# 7-segment.net
KiCad netlist of a schematic drawn in EAGLE
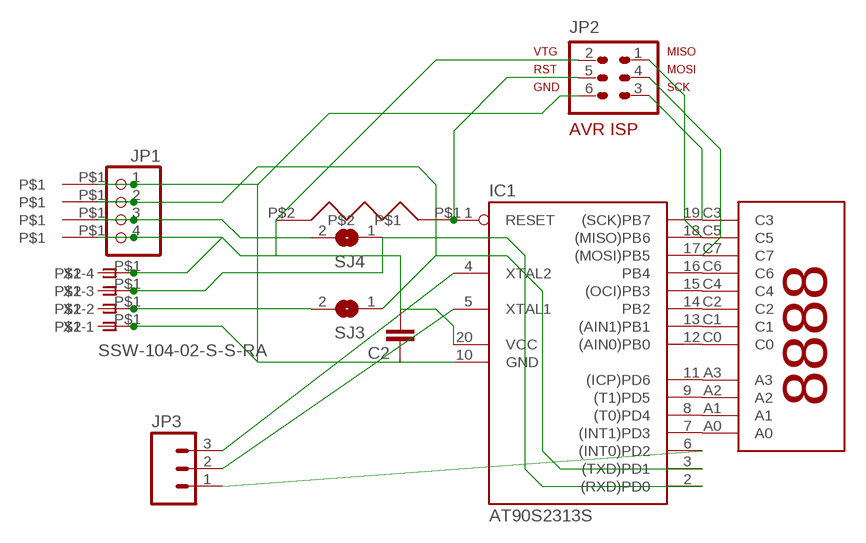
[diagram p0: schematic, sheet 1]

(export (version "E")
  (design (tool "Eeschema 10.0.6"))
  (components
    (comp (ref "C2")
      (value "CAPPTH")
      (footprint "eagle-import:CAP-PTH-SMALL")
      (libsource (lib "eagle-import") (part "CAPPTH"))
    )
    (comp (ref "IC1")
      (value "AT90S2313S")
      (footprint "eagle-import:SO20L")
      (libsource (lib "eagle-import") (part "AT90S2313S"))
    )
    (comp (ref "JP1")
      (value "PINHD-1X4/90")
      (footprint "eagle-import:1X04_90")
      (libsource (lib "eagle-import") (part "PINHD-1X4/90"))
    )
    (comp (ref "JP2")
      (value "AVR-ISP-6")
      (footprint "eagle-import:AVR-ISP-6")
      (libsource (lib "eagle-import") (part "AVR-ISP-6"))
    )
    (comp (ref "JP3")
      (value "M03PTH")
      (footprint "eagle-import:1X03")
      (libsource (lib "eagle-import") (part "M03PTH"))
    )
    (comp (ref "SJ3") (value "SJ") (footprint "eagle-import:SJ") (libsource (lib "eagle-import") (part "SJ")))
    (comp (ref "SJ4") (value "SJ") (footprint "eagle-import:SJ") (libsource (lib "eagle-import") (part "SJ")))
    (comp (ref "U$1")
      (value "7-SEGMENT-DISPLAY-5462-BS")
      (footprint "eagle-import:7SEG_5462BS")
      (libsource (lib "eagle-import") (part "7-SEGMENT-DISPLAY-5462-BS"))
    )
    (comp (ref "U$2")
      (value "R-6")
      (footprint "eagle-import:R-6")
      (libsource (lib "eagle-import") (part "R-6"))
    )
    (comp (ref "U$3")
      (value "WIREPAD_SQUARE_1")
      (footprint "eagle-import:WIREPAD_SQUARE_1")
      (libsource (lib "eagle-import") (part "WIREPAD_SQUARE_1"))
    )
    (comp (ref "U$4")
      (value "WIREPAD_SQUARE_1")
      (footprint "eagle-import:WIREPAD_SQUARE_1")
      (libsource (lib "eagle-import") (part "WIREPAD_SQUARE_1"))
    )
    (comp (ref "U$5")
      (value "WIREPAD_SQUARE_1")
      (footprint "eagle-import:WIREPAD_SQUARE_1")
      (libsource (lib "eagle-import") (part "WIREPAD_SQUARE_1"))
    )
    (comp (ref "U$6")
      (value "WIREPAD_SQUARE_1")
      (footprint "eagle-import:WIREPAD_SQUARE_1")
      (libsource (lib "eagle-import") (part "WIREPAD_SQUARE_1"))
    )
    (comp (ref "U$7")
      (value "WIREPAD_SQUARE_1")
      (footprint "eagle-import:WIREPAD_SQUARE_1")
      (libsource (lib "eagle-import") (part "WIREPAD_SQUARE_1"))
    )
    (comp (ref "U$8")
      (value "WIREPAD_SQUARE_1")
      (footprint "eagle-import:WIREPAD_SQUARE_1")
      (libsource (lib "eagle-import") (part "WIREPAD_SQUARE_1"))
    )
    (comp (ref "U$9")
      (value "WIREPAD_SQUARE_1")
      (footprint "eagle-import:WIREPAD_SQUARE_1")
      (libsource (lib "eagle-import") (part "WIREPAD_SQUARE_1"))
    )
    (comp (ref "U$10")
      (value "WIREPAD_SQUARE_1")
      (footprint "eagle-import:WIREPAD_SQUARE_1")
      (libsource (lib "eagle-import") (part "WIREPAD_SQUARE_1"))
    )
    (comp (ref "X2")
      (value "SSW-104-02-S-S-RA")
      (footprint "eagle-import:SSW-104-02-S-S-RA")
      (libsource (lib "eagle-import") (part "SSW-104-02-S-S-RA"))
    )
  )
  (nets
    (net (code "1") (name "Net-(IC1-(AIN0)PB0)") (class "Default")
      (node (ref "IC1") (pin "12") (pinfunction "(AIN0)PB0_12") (pintype "bidirectional"))
      (node (ref "U$1") (pin "C0") (pinfunction "C0_C0") (pintype "bidirectional"))
    )
    (net (code "2") (name "Net-(IC1-(AIN1)PB1)") (class "Default")
      (node (ref "IC1") (pin "13") (pinfunction "(AIN1)PB1_13") (pintype "bidirectional"))
      (node (ref "U$1") (pin "C1") (pinfunction "C1_C1") (pintype "bidirectional"))
    )
    (net (code "3") (name "Net-(IC1-(ICP)PD6)") (class "Default")
      (node (ref "IC1") (pin "11") (pinfunction "(ICP)PD6_11") (pintype "bidirectional"))
      (node (ref "U$1") (pin "A3") (pinfunction "A3_A3") (pintype "bidirectional"))
    )
    (net (code "4") (name "Net-(IC1-(INT0)PD2)") (class "Default")
      (node (ref "IC1") (pin "6") (pinfunction "(INT0)PD2_6") (pintype "bidirectional"))
      (node (ref "JP3") (pin "1") (pinfunction "1_1") (pintype "passive"))
    )
    (net (code "5") (name "Net-(IC1-(INT1)PD3)") (class "Default")
      (node (ref "IC1") (pin "7") (pinfunction "(INT1)PD3_7") (pintype "bidirectional"))
      (node (ref "U$1") (pin "A0") (pinfunction "A0_A0") (pintype "bidirectional"))
    )
    (net (code "6") (name "Net-(IC1-(MISO)PB6)") (class "Default")
      (node (ref "IC1") (pin "18") (pinfunction "(MISO)PB6_18") (pintype "bidirectional"))
      (node (ref "JP2") (pin "1") (pinfunction "1_1") (pintype "passive"))
      (node (ref "U$1") (pin "C5") (pinfunction "C5_C5") (pintype "bidirectional"))
    )
    (net (code "7") (name "Net-(IC1-(MOSI)PB5)") (class "Default")
      (node (ref "IC1") (pin "17") (pinfunction "(MOSI)PB5_17") (pintype "bidirectional"))
      (node (ref "JP2") (pin "4") (pinfunction "4_4") (pintype "passive"))
      (node (ref "U$1") (pin "C7") (pinfunction "C7_C7") (pintype "bidirectional"))
    )
    (net (code "8") (name "Net-(IC1-(OCI)PB3)") (class "Default")
      (node (ref "IC1") (pin "15") (pinfunction "(OCI)PB3_15") (pintype "bidirectional"))
      (node (ref "U$1") (pin "C4") (pinfunction "C4_C4") (pintype "bidirectional"))
    )
    (net (code "9") (name "Net-(IC1-(RXD)PD0)") (class "Default")
      (node (ref "IC1") (pin "2") (pinfunction "(RXD)PD0_2") (pintype "bidirectional"))
      (node (ref "SJ4") (pin "1") (pinfunction "1_1") (pintype "passive"))
      (node (ref "U$8") (pin "P$1") (pinfunction "P$1_P$1") (pintype "bidirectional"))
      (node (ref "X2") (pin "3") (pinfunction "1_3") (pintype "passive"))
    )
    (net (code "10") (name "Net-(IC1-(SCK)PB7)") (class "Default")
      (node (ref "IC1") (pin "19") (pinfunction "(SCK)PB7_19") (pintype "bidirectional"))
      (node (ref "JP2") (pin "3") (pinfunction "3_3") (pintype "passive"))
      (node (ref "U$1") (pin "C3") (pinfunction "C3_C3") (pintype "bidirectional"))
    )
    (net (code "11") (name "Net-(IC1-(T0)PD4)") (class "Default")
      (node (ref "IC1") (pin "8") (pinfunction "(T0)PD4_8") (pintype "bidirectional"))
      (node (ref "U$1") (pin "A1") (pinfunction "A1_A1") (pintype "bidirectional"))
    )
    (net (code "12") (name "Net-(IC1-(T1)PD5)") (class "Default")
      (node (ref "IC1") (pin "9") (pinfunction "(T1)PD5_9") (pintype "bidirectional"))
      (node (ref "U$1") (pin "A2") (pinfunction "A2_A2") (pintype "bidirectional"))
    )
    (net (code "13") (name "Net-(IC1-(TXD)PD1)") (class "Default")
      (node (ref "IC1") (pin "3") (pinfunction "(TXD)PD1_3") (pintype "bidirectional"))
      (node (ref "JP1") (pin "2") (pinfunction "2_2") (pintype "passive"))
      (node (ref "SJ3") (pin "1") (pinfunction "1_1") (pintype "passive"))
      (node (ref "U$4") (pin "P$1") (pinfunction "P$1_P$1") (pintype "bidirectional"))
    )
    (net (code "14") (name "Net-(IC1-GND)") (class "Default")
      (node (ref "C2") (pin "1") (pinfunction "1_1") (pintype "passive"))
      (node (ref "IC1") (pin "10") (pinfunction "GND_10") (pintype "power_in"))
      (node (ref "JP1") (pin "1") (pinfunction "1_1") (pintype "passive"))
      (node (ref "JP2") (pin "6") (pinfunction "6_6") (pintype "passive"))
      (node (ref "U$10") (pin "P$1") (pinfunction "P$1_P$1") (pintype "bidirectional"))
      (node (ref "U$3") (pin "P$1") (pinfunction "P$1_P$1") (pintype "bidirectional"))
      (node (ref "X2") (pin "1") (pinfunction "1_1") (pintype "passive"))
    )
    (net (code "15") (name "Net-(IC1-PB2)") (class "Default")
      (node (ref "IC1") (pin "14") (pinfunction "PB2_14") (pintype "bidirectional"))
      (node (ref "U$1") (pin "C2") (pinfunction "C2_C2") (pintype "bidirectional"))
    )
    (net (code "16") (name "Net-(IC1-PB4)") (class "Default")
      (node (ref "IC1") (pin "16") (pinfunction "PB4_16") (pintype "bidirectional"))
      (node (ref "U$1") (pin "C6") (pinfunction "C6_C6") (pintype "bidirectional"))
    )
    (net (code "17") (name "Net-(IC1-RESET)") (class "Default")
      (node (ref "IC1") (pin "1") (pinfunction "RESET_1") (pintype "bidirectional"))
      (node (ref "JP2") (pin "5") (pinfunction "5_5") (pintype "passive"))
      (node (ref "U$2") (pin "P$1") (pinfunction "P$1_P$1") (pintype "bidirectional"))
    )
    (net (code "18") (name "Net-(IC1-VCC)") (class "Default")
      (node (ref "C2") (pin "2") (pinfunction "2_2") (pintype "passive"))
      (node (ref "IC1") (pin "20") (pinfunction "VCC_20") (pintype "power_in"))
      (node (ref "JP1") (pin "4") (pinfunction "4_4") (pintype "passive"))
      (node (ref "JP2") (pin "2") (pinfunction "2_2") (pintype "passive"))
      (node (ref "U$2") (pin "P$2") (pinfunction "P$2_P$2") (pintype "bidirectional"))
      (node (ref "U$6") (pin "P$1") (pinfunction "P$1_P$1") (pintype "bidirectional"))
      (node (ref "U$7") (pin "P$1") (pinfunction "P$1_P$1") (pintype "bidirectional"))
      (node (ref "X2") (pin "4") (pinfunction "1_4") (pintype "passive"))
    )
    (net (code "19") (name "Net-(IC1-XTAL1)") (class "Default")
      (node (ref "IC1") (pin "5") (pinfunction "XTAL1_5") (pintype "bidirectional"))
      (node (ref "JP3") (pin "2") (pinfunction "2_2") (pintype "passive"))
    )
    (net (code "20") (name "Net-(IC1-XTAL2)") (class "Default")
      (node (ref "IC1") (pin "4") (pinfunction "XTAL2_4") (pintype "bidirectional"))
      (node (ref "JP3") (pin "3") (pinfunction "3_3") (pintype "passive"))
    )
    (net (code "21") (name "Net-(JP1-Pad3)") (class "Default")
      (node (ref "JP1") (pin "3") (pinfunction "3_3") (pintype "passive"))
      (node (ref "SJ4") (pin "2") (pinfunction "2_2") (pintype "passive"))
      (node (ref "U$5") (pin "P$1") (pinfunction "P$1_P$1") (pintype "bidirectional"))
    )
    (net (code "22") (name "Net-(X2B-1)") (class "Default")
      (node (ref "SJ3") (pin "2") (pinfunction "2_2") (pintype "passive"))
      (node (ref "U$9") (pin "P$1") (pinfunction "P$1_P$1") (pintype "bidirectional"))
      (node (ref "X2") (pin "2") (pinfunction "1_2") (pintype "passive"))
    )
  )
)
